# solenoid-shield.net
KiCad netlist of a schematic drawn in EAGLE
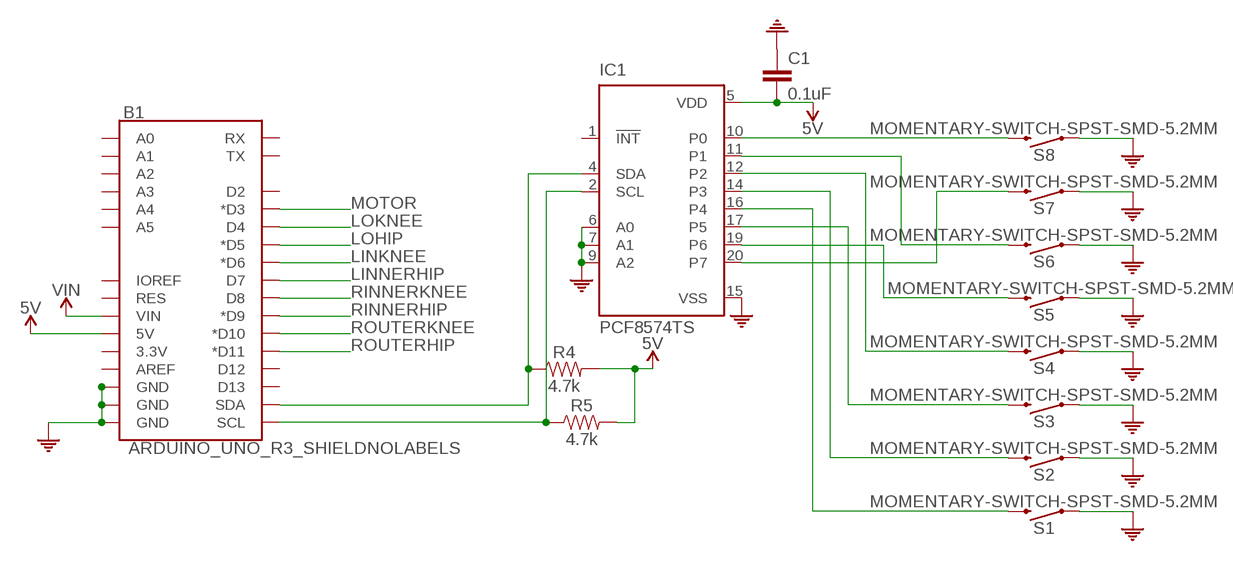
[diagram p0: schematic, sheet 1]
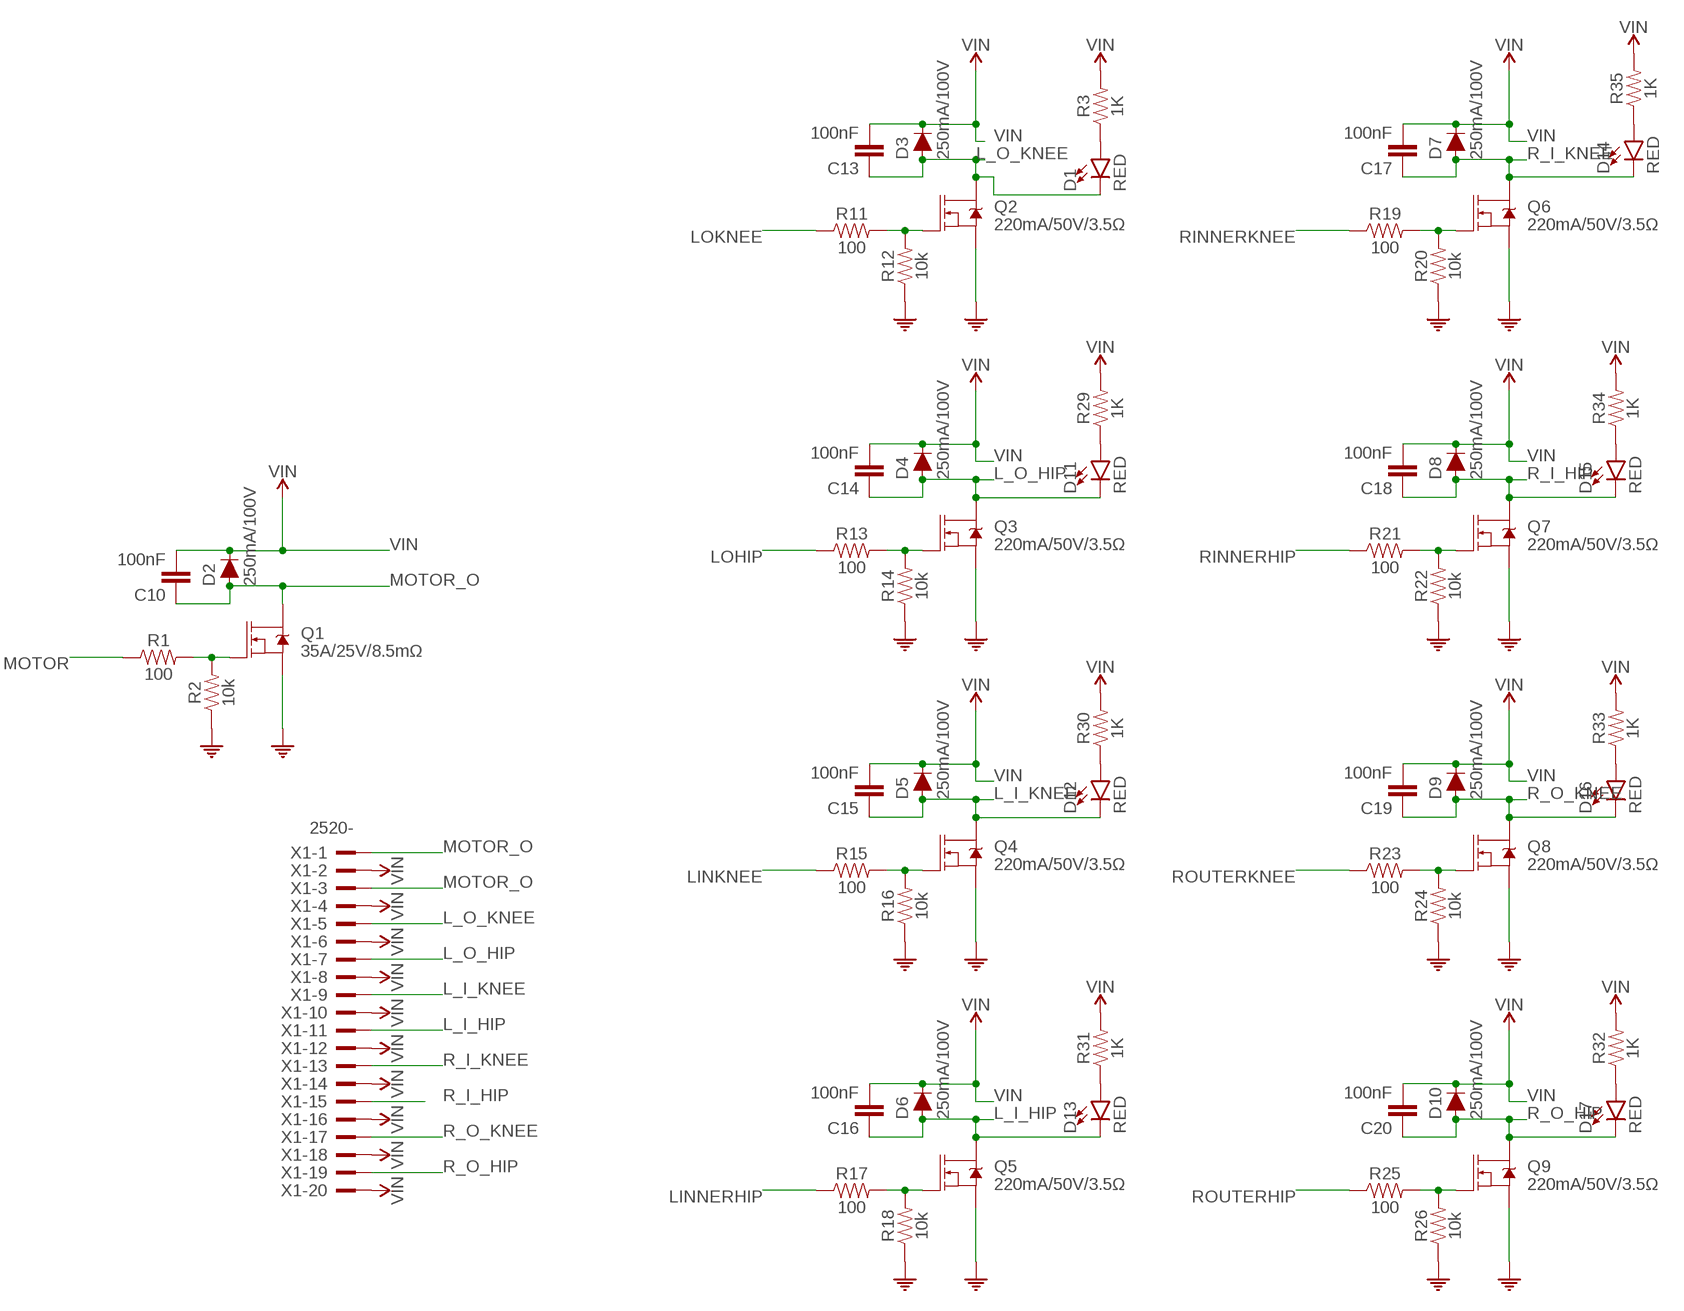
[diagram p1: schematic, sheet 2]

(export (version "E")
  (design (tool "Eeschema 10.0.6"))
  (components
    (comp (ref "B1")
      (value "ARDUINO_UNO_R3_SHIELDNOLABELS")
      (footprint "eagle-import:UNO_R3_SHIELD_NOLABELS")
      (libsource (lib "eagle-import") (part "ARDUINO_UNO_R3_SHIELDNOLABELS"))
    )
    (comp (ref "C1")
      (value "0.1uF")
      (footprint "eagle-import:0603")
      (libsource (lib "eagle-import") (part "0.1UF-0603-25V-5%"))
    )
    (comp (ref "IC1")
      (value "PCF8574TS")
      (footprint "eagle-import:SSOP20")
      (fields (field (name "MPN") "PCF8574TS/3,118"))
      (libsource (lib "eagle-import") (part "PCF8574TS"))
    )
    (comp (ref "R4")
      (value "4.7k")
      (footprint "eagle-import:0603")
      (libsource (lib "eagle-import") (part "4.7KOHM-0603-1/10W-1%"))
    )
    (comp (ref "R5")
      (value "4.7k")
      (footprint "eagle-import:0603")
      (libsource (lib "eagle-import") (part "4.7KOHM-0603-1/10W-1%"))
    )
    (comp (ref "S1")
      (value "MOMENTARY-SWITCH-SPST-SMD-5.2MM")
      (footprint "eagle-import:TACTILE_SWITCH_SMD_5.2MM")
      (libsource (lib "eagle-import") (part "MOMENTARY-SWITCH-SPST-SMD-5.2MM"))
    )
    (comp (ref "S2")
      (value "MOMENTARY-SWITCH-SPST-SMD-5.2MM")
      (footprint "eagle-import:TACTILE_SWITCH_SMD_5.2MM")
      (libsource (lib "eagle-import") (part "MOMENTARY-SWITCH-SPST-SMD-5.2MM"))
    )
    (comp (ref "S3")
      (value "MOMENTARY-SWITCH-SPST-SMD-5.2MM")
      (footprint "eagle-import:TACTILE_SWITCH_SMD_5.2MM")
      (libsource (lib "eagle-import") (part "MOMENTARY-SWITCH-SPST-SMD-5.2MM"))
    )
    (comp (ref "S4")
      (value "MOMENTARY-SWITCH-SPST-SMD-5.2MM")
      (footprint "eagle-import:TACTILE_SWITCH_SMD_5.2MM")
      (libsource (lib "eagle-import") (part "MOMENTARY-SWITCH-SPST-SMD-5.2MM"))
    )
    (comp (ref "S5")
      (value "MOMENTARY-SWITCH-SPST-SMD-5.2MM")
      (footprint "eagle-import:TACTILE_SWITCH_SMD_5.2MM")
      (libsource (lib "eagle-import") (part "MOMENTARY-SWITCH-SPST-SMD-5.2MM"))
    )
    (comp (ref "S6")
      (value "MOMENTARY-SWITCH-SPST-SMD-5.2MM")
      (footprint "eagle-import:TACTILE_SWITCH_SMD_5.2MM")
      (libsource (lib "eagle-import") (part "MOMENTARY-SWITCH-SPST-SMD-5.2MM"))
    )
    (comp (ref "S7")
      (value "MOMENTARY-SWITCH-SPST-SMD-5.2MM")
      (footprint "eagle-import:TACTILE_SWITCH_SMD_5.2MM")
      (libsource (lib "eagle-import") (part "MOMENTARY-SWITCH-SPST-SMD-5.2MM"))
    )
    (comp (ref "S8")
      (value "MOMENTARY-SWITCH-SPST-SMD-5.2MM")
      (footprint "eagle-import:TACTILE_SWITCH_SMD_5.2MM")
      (libsource (lib "eagle-import") (part "MOMENTARY-SWITCH-SPST-SMD-5.2MM"))
    )
    (comp (ref "C10")
      (value "100nF")
      (footprint "eagle-import:C0603-ROUND")
      (fields (field (name "PART_NUMBER") "cl10b104kbnc"))
      (libsource (lib "eagle-import") (part "0015_100NF_0603"))
    )
    (comp (ref "C13")
      (value "100nF")
      (footprint "eagle-import:C0603-ROUND")
      (fields (field (name "PART_NUMBER") "cl10b104kbnc"))
      (libsource (lib "eagle-import") (part "0015_100NF_0603"))
    )
    (comp (ref "C14")
      (value "100nF")
      (footprint "eagle-import:C0603-ROUND")
      (fields (field (name "PART_NUMBER") "cl10b104kbnc"))
      (libsource (lib "eagle-import") (part "0015_100NF_0603"))
    )
    (comp (ref "C15")
      (value "100nF")
      (footprint "eagle-import:C0603-ROUND")
      (fields (field (name "PART_NUMBER") "cl10b104kbnc"))
      (libsource (lib "eagle-import") (part "0015_100NF_0603"))
    )
    (comp (ref "C16")
      (value "100nF")
      (footprint "eagle-import:C0603-ROUND")
      (fields (field (name "PART_NUMBER") "cl10b104kbnc"))
      (libsource (lib "eagle-import") (part "0015_100NF_0603"))
    )
    (comp (ref "C17")
      (value "100nF")
      (footprint "eagle-import:C0603-ROUND")
      (fields (field (name "PART_NUMBER") "cl10b104kbnc"))
      (libsource (lib "eagle-import") (part "0015_100NF_0603"))
    )
    (comp (ref "C18")
      (value "100nF")
      (footprint "eagle-import:C0603-ROUND")
      (fields (field (name "PART_NUMBER") "cl10b104kbnc"))
      (libsource (lib "eagle-import") (part "0015_100NF_0603"))
    )
    (comp (ref "C19")
      (value "100nF")
      (footprint "eagle-import:C0603-ROUND")
      (fields (field (name "PART_NUMBER") "cl10b104kbnc"))
      (libsource (lib "eagle-import") (part "0015_100NF_0603"))
    )
    (comp (ref "C20")
      (value "100nF")
      (footprint "eagle-import:C0603-ROUND")
      (fields (field (name "PART_NUMBER") "cl10b104kbnc"))
      (libsource (lib "eagle-import") (part "0015_100NF_0603"))
    )
    (comp (ref "D1")
      (value "RED")
      (footprint "eagle-import:LED-0603")
      (libsource (lib "eagle-import") (part "LED-RED0603"))
    )
    (comp (ref "D2")
      (value "250mA/100V")
      (footprint "eagle-import:SOD-323")
      (libsource (lib "eagle-import") (part "DIODE-BAS16J"))
    )
    (comp (ref "D3")
      (value "250mA/100V")
      (footprint "eagle-import:SOD-323")
      (libsource (lib "eagle-import") (part "DIODE-BAS16J"))
    )
    (comp (ref "D4")
      (value "250mA/100V")
      (footprint "eagle-import:SOD-323")
      (libsource (lib "eagle-import") (part "DIODE-BAS16J"))
    )
    (comp (ref "D5")
      (value "250mA/100V")
      (footprint "eagle-import:SOD-323")
      (libsource (lib "eagle-import") (part "DIODE-BAS16J"))
    )
    (comp (ref "D6")
      (value "250mA/100V")
      (footprint "eagle-import:SOD-323")
      (libsource (lib "eagle-import") (part "DIODE-BAS16J"))
    )
    (comp (ref "D7")
      (value "250mA/100V")
      (footprint "eagle-import:SOD-323")
      (libsource (lib "eagle-import") (part "DIODE-BAS16J"))
    )
    (comp (ref "D8")
      (value "250mA/100V")
      (footprint "eagle-import:SOD-323")
      (libsource (lib "eagle-import") (part "DIODE-BAS16J"))
    )
    (comp (ref "D9")
      (value "250mA/100V")
      (footprint "eagle-import:SOD-323")
      (libsource (lib "eagle-import") (part "DIODE-BAS16J"))
    )
    (comp (ref "D10")
      (value "250mA/100V")
      (footprint "eagle-import:SOD-323")
      (libsource (lib "eagle-import") (part "DIODE-BAS16J"))
    )
    (comp (ref "D11")
      (value "RED")
      (footprint "eagle-import:LED-0603")
      (libsource (lib "eagle-import") (part "LED-RED0603"))
    )
    (comp (ref "D12")
      (value "RED")
      (footprint "eagle-import:LED-0603")
      (libsource (lib "eagle-import") (part "LED-RED0603"))
    )
    (comp (ref "D13")
      (value "RED")
      (footprint "eagle-import:LED-0603")
      (libsource (lib "eagle-import") (part "LED-RED0603"))
    )
    (comp (ref "D14")
      (value "RED")
      (footprint "eagle-import:LED-0603")
      (libsource (lib "eagle-import") (part "LED-RED0603"))
    )
    (comp (ref "D15")
      (value "RED")
      (footprint "eagle-import:LED-0603")
      (libsource (lib "eagle-import") (part "LED-RED0603"))
    )
    (comp (ref "D16")
      (value "RED")
      (footprint "eagle-import:LED-0603")
      (libsource (lib "eagle-import") (part "LED-RED0603"))
    )
    (comp (ref "D17")
      (value "RED")
      (footprint "eagle-import:LED-0603")
      (libsource (lib "eagle-import") (part "LED-RED0603"))
    )
    (comp (ref "Q1")
      (value "35A/25V/8.5mΩ")
      (footprint "eagle-import:DPAK")
      (libsource (lib "eagle-import") (part "MOSFET-NCH-FDD8780"))
    )
    (comp (ref "Q2")
      (value "220mA/50V/3.5Ω")
      (footprint "eagle-import:SOT23-3")
      (libsource (lib "eagle-import") (part "MOSFET-NCH-BSS138"))
    )
    (comp (ref "Q3")
      (value "220mA/50V/3.5Ω")
      (footprint "eagle-import:SOT23-3")
      (libsource (lib "eagle-import") (part "MOSFET-NCH-BSS138"))
    )
    (comp (ref "Q4")
      (value "220mA/50V/3.5Ω")
      (footprint "eagle-import:SOT23-3")
      (libsource (lib "eagle-import") (part "MOSFET-NCH-BSS138"))
    )
    (comp (ref "Q5")
      (value "220mA/50V/3.5Ω")
      (footprint "eagle-import:SOT23-3")
      (libsource (lib "eagle-import") (part "MOSFET-NCH-BSS138"))
    )
    (comp (ref "Q6")
      (value "220mA/50V/3.5Ω")
      (footprint "eagle-import:SOT23-3")
      (libsource (lib "eagle-import") (part "MOSFET-NCH-BSS138"))
    )
    (comp (ref "Q7")
      (value "220mA/50V/3.5Ω")
      (footprint "eagle-import:SOT23-3")
      (libsource (lib "eagle-import") (part "MOSFET-NCH-BSS138"))
    )
    (comp (ref "Q8")
      (value "220mA/50V/3.5Ω")
      (footprint "eagle-import:SOT23-3")
      (libsource (lib "eagle-import") (part "MOSFET-NCH-BSS138"))
    )
    (comp (ref "Q9")
      (value "220mA/50V/3.5Ω")
      (footprint "eagle-import:SOT23-3")
      (libsource (lib "eagle-import") (part "MOSFET-NCH-BSS138"))
    )
    (comp (ref "R1")
      (value "100")
      (footprint "eagle-import:0603")
      (libsource (lib "eagle-import") (part "100OHM-0603-1/10W-1%"))
    )
    (comp (ref "R2")
      (value "10k")
      (footprint "eagle-import:0603")
      (libsource (lib "eagle-import") (part "10KOHM-0603-1/10W-1%"))
    )
    (comp (ref "R3")
      (value "1K")
      (footprint "eagle-import:0603")
      (libsource (lib "eagle-import") (part "10KOHM-0603-1/10W-1%"))
    )
    (comp (ref "R11")
      (value "100")
      (footprint "eagle-import:0603")
      (libsource (lib "eagle-import") (part "100OHM-0603-1/10W-1%"))
    )
    (comp (ref "R12")
      (value "10k")
      (footprint "eagle-import:0603")
      (libsource (lib "eagle-import") (part "10KOHM-0603-1/10W-1%"))
    )
    (comp (ref "R13")
      (value "100")
      (footprint "eagle-import:0603")
      (libsource (lib "eagle-import") (part "100OHM-0603-1/10W-1%"))
    )
    (comp (ref "R14")
      (value "10k")
      (footprint "eagle-import:0603")
      (libsource (lib "eagle-import") (part "10KOHM-0603-1/10W-1%"))
    )
    (comp (ref "R15")
      (value "100")
      (footprint "eagle-import:0603")
      (libsource (lib "eagle-import") (part "100OHM-0603-1/10W-1%"))
    )
    (comp (ref "R16")
      (value "10k")
      (footprint "eagle-import:0603")
      (libsource (lib "eagle-import") (part "10KOHM-0603-1/10W-1%"))
    )
    (comp (ref "R17")
      (value "100")
      (footprint "eagle-import:0603")
      (libsource (lib "eagle-import") (part "100OHM-0603-1/10W-1%"))
    )
    (comp (ref "R18")
      (value "10k")
      (footprint "eagle-import:0603")
      (libsource (lib "eagle-import") (part "10KOHM-0603-1/10W-1%"))
    )
    (comp (ref "R19")
      (value "100")
      (footprint "eagle-import:0603")
      (libsource (lib "eagle-import") (part "100OHM-0603-1/10W-1%"))
    )
    (comp (ref "R20")
      (value "10k")
      (footprint "eagle-import:0603")
      (libsource (lib "eagle-import") (part "10KOHM-0603-1/10W-1%"))
    )
    (comp (ref "R21")
      (value "100")
      (footprint "eagle-import:0603")
      (libsource (lib "eagle-import") (part "100OHM-0603-1/10W-1%"))
    )
    (comp (ref "R22")
      (value "10k")
      (footprint "eagle-import:0603")
      (libsource (lib "eagle-import") (part "10KOHM-0603-1/10W-1%"))
    )
    (comp (ref "R23")
      (value "100")
      (footprint "eagle-import:0603")
      (libsource (lib "eagle-import") (part "100OHM-0603-1/10W-1%"))
    )
    (comp (ref "R24")
      (value "10k")
      (footprint "eagle-import:0603")
      (libsource (lib "eagle-import") (part "10KOHM-0603-1/10W-1%"))
    )
    (comp (ref "R25")
      (value "100")
      (footprint "eagle-import:0603")
      (libsource (lib "eagle-import") (part "100OHM-0603-1/10W-1%"))
    )
    (comp (ref "R26")
      (value "10k")
      (footprint "eagle-import:0603")
      (libsource (lib "eagle-import") (part "10KOHM-0603-1/10W-1%"))
    )
    (comp (ref "R29")
      (value "1K")
      (footprint "eagle-import:0603")
      (libsource (lib "eagle-import") (part "10KOHM-0603-1/10W-1%"))
    )
    (comp (ref "R30")
      (value "1K")
      (footprint "eagle-import:0603")
      (libsource (lib "eagle-import") (part "10KOHM-0603-1/10W-1%"))
    )
    (comp (ref "R31")
      (value "1K")
      (footprint "eagle-import:0603")
      (libsource (lib "eagle-import") (part "10KOHM-0603-1/10W-1%"))
    )
    (comp (ref "R32")
      (value "1K")
      (footprint "eagle-import:0603")
      (libsource (lib "eagle-import") (part "10KOHM-0603-1/10W-1%"))
    )
    (comp (ref "R33")
      (value "1K")
      (footprint "eagle-import:0603")
      (libsource (lib "eagle-import") (part "10KOHM-0603-1/10W-1%"))
    )
    (comp (ref "R34")
      (value "1K")
      (footprint "eagle-import:0603")
      (libsource (lib "eagle-import") (part "10KOHM-0603-1/10W-1%"))
    )
    (comp (ref "R35")
      (value "1K")
      (footprint "eagle-import:0603")
      (libsource (lib "eagle-import") (part "10KOHM-0603-1/10W-1%"))
    )
    (comp (ref "X1")
      (value "2520-")
      (footprint "eagle-import:PAK100_2500-20")
      (libsource (lib "eagle-import") (part "2520-"))
    )
  )
  (nets
    (net (code "1") (name "5V") (class "Default")
      (node (ref "B1") (pin "5V") (pinfunction "5V_5V") (pintype "bidirectional"))
      (node (ref "C1") (pin "2") (pinfunction "2_2") (pintype "passive"))
      (node (ref "IC1") (pin "5") (pinfunction "VDD_5") (pintype "power_in"))
      (node (ref "R4") (pin "2") (pinfunction "2_2") (pintype "passive"))
      (node (ref "R5") (pin "2") (pinfunction "2_2") (pintype "passive"))
    )
    (net (code "2") (name "COM") (class "Default")
      (node (ref "B1") (pin "GND@0") (pinfunction "GND_GND@0") (pintype "bidirectional"))
      (node (ref "B1") (pin "GND@1") (pinfunction "GND_GND@1") (pintype "bidirectional"))
      (node (ref "B1") (pin "GND@2") (pinfunction "GND_GND@2") (pintype "bidirectional"))
      (node (ref "C1") (pin "1") (pinfunction "1_1") (pintype "passive"))
      (node (ref "IC1") (pin "15") (pinfunction "VSS_15") (pintype "power_in"))
      (node (ref "IC1") (pin "6") (pinfunction "A0_6") (pintype "input"))
      (node (ref "IC1") (pin "7") (pinfunction "A1_7") (pintype "input"))
      (node (ref "IC1") (pin "9") (pinfunction "A2_9") (pintype "input"))
      (node (ref "Q1") (pin "3") (pinfunction "S_3") (pintype "bidirectional"))
      (node (ref "Q2") (pin "2") (pinfunction "S_2") (pintype "bidirectional"))
      (node (ref "Q3") (pin "2") (pinfunction "S_2") (pintype "bidirectional"))
      (node (ref "Q4") (pin "2") (pinfunction "S_2") (pintype "bidirectional"))
      (node (ref "Q5") (pin "2") (pinfunction "S_2") (pintype "bidirectional"))
      (node (ref "Q6") (pin "2") (pinfunction "S_2") (pintype "bidirectional"))
      (node (ref "Q7") (pin "2") (pinfunction "S_2") (pintype "bidirectional"))
      (node (ref "Q8") (pin "2") (pinfunction "S_2") (pintype "bidirectional"))
      (node (ref "Q9") (pin "2") (pinfunction "S_2") (pintype "bidirectional"))
      (node (ref "R12") (pin "1") (pinfunction "1_1") (pintype "passive"))
      (node (ref "R14") (pin "1") (pinfunction "1_1") (pintype "passive"))
      (node (ref "R16") (pin "1") (pinfunction "1_1") (pintype "passive"))
      (node (ref "R18") (pin "1") (pinfunction "1_1") (pintype "passive"))
      (node (ref "R2") (pin "1") (pinfunction "1_1") (pintype "passive"))
      (node (ref "R20") (pin "1") (pinfunction "1_1") (pintype "passive"))
      (node (ref "R22") (pin "1") (pinfunction "1_1") (pintype "passive"))
      (node (ref "R24") (pin "1") (pinfunction "1_1") (pintype "passive"))
      (node (ref "R26") (pin "1") (pinfunction "1_1") (pintype "passive"))
      (node (ref "S1") (pin "1") (pinfunction "1_1") (pintype "passive"))
      (node (ref "S2") (pin "1") (pinfunction "1_1") (pintype "passive"))
      (node (ref "S3") (pin "1") (pinfunction "1_1") (pintype "passive"))
      (node (ref "S4") (pin "1") (pinfunction "1_1") (pintype "passive"))
      (node (ref "S5") (pin "1") (pinfunction "1_1") (pintype "passive"))
      (node (ref "S6") (pin "1") (pinfunction "1_1") (pintype "passive"))
      (node (ref "S7") (pin "1") (pinfunction "1_1") (pintype "passive"))
      (node (ref "S8") (pin "1") (pinfunction "1_1") (pintype "passive"))
    )
    (net (code "3") (name "LINKNEE") (class "Default")
      (node (ref "B1") (pin "D6") (pinfunction "*D6_D6") (pintype "bidirectional"))
      (node (ref "R15") (pin "1") (pinfunction "1_1") (pintype "passive"))
    )
    (net (code "4") (name "LINNERHIP") (class "Default")
      (node (ref "B1") (pin "D7") (pinfunction "D7_D7") (pintype "bidirectional"))
      (node (ref "R17") (pin "1") (pinfunction "1_1") (pintype "passive"))
    )
    (net (code "5") (name "LOHIP") (class "Default")
      (node (ref "B1") (pin "D5") (pinfunction "*D5_D5") (pintype "bidirectional"))
      (node (ref "R13") (pin "1") (pinfunction "1_1") (pintype "passive"))
    )
    (net (code "6") (name "LOKNEE") (class "Default")
      (node (ref "B1") (pin "D4") (pinfunction "D4_D4") (pintype "bidirectional"))
      (node (ref "R11") (pin "1") (pinfunction "1_1") (pintype "passive"))
    )
    (net (code "7") (name "L_I_HIP") (class "Default")
      (node (ref "C16") (pin "1") (pinfunction "1_1") (pintype "passive"))
      (node (ref "D13") (pin "C") (pinfunction "C_C") (pintype "passive"))
      (node (ref "D6") (pin "A") (pinfunction "A_A") (pintype "passive"))
      (node (ref "Q5") (pin "3") (pinfunction "D_3") (pintype "bidirectional"))
      (node (ref "X1") (pin "11") (pinfunction "KL_11") (pintype "passive"))
    )
    (net (code "8") (name "L_I_KNEE") (class "Default")
      (node (ref "C15") (pin "1") (pinfunction "1_1") (pintype "passive"))
      (node (ref "D12") (pin "C") (pinfunction "C_C") (pintype "passive"))
      (node (ref "D5") (pin "A") (pinfunction "A_A") (pintype "passive"))
      (node (ref "Q4") (pin "3") (pinfunction "D_3") (pintype "bidirectional"))
      (node (ref "X1") (pin "9") (pinfunction "KL_9") (pintype "passive"))
    )
    (net (code "9") (name "L_O_HIP") (class "Default")
      (node (ref "C14") (pin "1") (pinfunction "1_1") (pintype "passive"))
      (node (ref "D11") (pin "C") (pinfunction "C_C") (pintype "passive"))
      (node (ref "D4") (pin "A") (pinfunction "A_A") (pintype "passive"))
      (node (ref "Q3") (pin "3") (pinfunction "D_3") (pintype "bidirectional"))
      (node (ref "X1") (pin "7") (pinfunction "KL_7") (pintype "passive"))
    )
    (net (code "10") (name "L_O_KNEE") (class "Default")
      (node (ref "C13") (pin "1") (pinfunction "1_1") (pintype "passive"))
      (node (ref "D1") (pin "C") (pinfunction "C_C") (pintype "passive"))
      (node (ref "D3") (pin "A") (pinfunction "A_A") (pintype "passive"))
      (node (ref "Q2") (pin "3") (pinfunction "D_3") (pintype "bidirectional"))
      (node (ref "X1") (pin "5") (pinfunction "KL_5") (pintype "passive"))
    )
    (net (code "11") (name "MOTOR") (class "Default")
      (node (ref "B1") (pin "D3") (pinfunction "*D3_D3") (pintype "bidirectional"))
      (node (ref "R1") (pin "1") (pinfunction "1_1") (pintype "passive"))
    )
    (net (code "12") (name "MOTOR_O") (class "Default")
      (node (ref "C10") (pin "1") (pinfunction "1_1") (pintype "passive"))
      (node (ref "D2") (pin "A") (pinfunction "A_A") (pintype "passive"))
      (node (ref "Q1") (pin "4") (pinfunction "D_4") (pintype "bidirectional"))
      (node (ref "X1") (pin "1") (pinfunction "KL_1") (pintype "passive"))
      (node (ref "X1") (pin "3") (pinfunction "KL_3") (pintype "passive"))
    )
    (net (code "13") (name "Net-(D1-PadA)") (class "Default")
      (node (ref "D1") (pin "A") (pinfunction "A_A") (pintype "passive"))
      (node (ref "R3") (pin "1") (pinfunction "1_1") (pintype "passive"))
    )
    (net (code "14") (name "Net-(D11-PadA)") (class "Default")
      (node (ref "D11") (pin "A") (pinfunction "A_A") (pintype "passive"))
      (node (ref "R29") (pin "1") (pinfunction "1_1") (pintype "passive"))
    )
    (net (code "15") (name "Net-(D12-PadA)") (class "Default")
      (node (ref "D12") (pin "A") (pinfunction "A_A") (pintype "passive"))
      (node (ref "R30") (pin "1") (pinfunction "1_1") (pintype "passive"))
    )
    (net (code "16") (name "Net-(D13-PadA)") (class "Default")
      (node (ref "D13") (pin "A") (pinfunction "A_A") (pintype "passive"))
      (node (ref "R31") (pin "1") (pinfunction "1_1") (pintype "passive"))
    )
    (net (code "17") (name "Net-(D14-PadA)") (class "Default")
      (node (ref "D14") (pin "A") (pinfunction "A_A") (pintype "passive"))
      (node (ref "R35") (pin "1") (pinfunction "1_1") (pintype "passive"))
    )
    (net (code "18") (name "Net-(D15-PadA)") (class "Default")
      (node (ref "D15") (pin "A") (pinfunction "A_A") (pintype "passive"))
      (node (ref "R34") (pin "1") (pinfunction "1_1") (pintype "passive"))
    )
    (net (code "19") (name "Net-(D16-PadA)") (class "Default")
      (node (ref "D16") (pin "A") (pinfunction "A_A") (pintype "passive"))
      (node (ref "R33") (pin "1") (pinfunction "1_1") (pintype "passive"))
    )
    (net (code "20") (name "Net-(D17-PadA)") (class "Default")
      (node (ref "D17") (pin "A") (pinfunction "A_A") (pintype "passive"))
      (node (ref "R32") (pin "1") (pinfunction "1_1") (pintype "passive"))
    )
    (net (code "21") (name "Net-(IC1-P0)") (class "Default")
      (node (ref "IC1") (pin "10") (pinfunction "P0_10") (pintype "bidirectional"))
      (node (ref "S8") (pin "3") (pinfunction "2_3") (pintype "passive"))
    )
    (net (code "22") (name "Net-(IC1-P1)") (class "Default")
      (node (ref "IC1") (pin "11") (pinfunction "P1_11") (pintype "bidirectional"))
      (node (ref "S6") (pin "3") (pinfunction "2_3") (pintype "passive"))
    )
    (net (code "23") (name "Net-(IC1-P2)") (class "Default")
      (node (ref "IC1") (pin "12") (pinfunction "P2_12") (pintype "bidirectional"))
      (node (ref "S4") (pin "3") (pinfunction "2_3") (pintype "passive"))
    )
    (net (code "24") (name "Net-(IC1-P3)") (class "Default")
      (node (ref "IC1") (pin "14") (pinfunction "P3_14") (pintype "bidirectional"))
      (node (ref "S2") (pin "3") (pinfunction "2_3") (pintype "passive"))
    )
    (net (code "25") (name "Net-(IC1-P4)") (class "Default")
      (node (ref "IC1") (pin "16") (pinfunction "P4_16") (pintype "bidirectional"))
      (node (ref "S1") (pin "3") (pinfunction "2_3") (pintype "passive"))
    )
    (net (code "26") (name "Net-(IC1-P5)") (class "Default")
      (node (ref "IC1") (pin "17") (pinfunction "P5_17") (pintype "bidirectional"))
      (node (ref "S3") (pin "3") (pinfunction "2_3") (pintype "passive"))
    )
    (net (code "27") (name "Net-(IC1-P6)") (class "Default")
      (node (ref "IC1") (pin "19") (pinfunction "P6_19") (pintype "bidirectional"))
      (node (ref "S5") (pin "3") (pinfunction "2_3") (pintype "passive"))
    )
    (net (code "28") (name "Net-(IC1-P7)") (class "Default")
      (node (ref "IC1") (pin "20") (pinfunction "P7_20") (pintype "bidirectional"))
      (node (ref "S7") (pin "3") (pinfunction "2_3") (pintype "passive"))
    )
    (net (code "29") (name "Net-(IC1-SCL)") (class "Default")
      (node (ref "B1") (pin "SCL") (pinfunction "SCL_SCL") (pintype "bidirectional"))
      (node (ref "IC1") (pin "2") (pinfunction "SCL_2") (pintype "input"))
      (node (ref "R5") (pin "1") (pinfunction "1_1") (pintype "passive"))
    )
    (net (code "30") (name "Net-(IC1-SDA)") (class "Default")
      (node (ref "B1") (pin "SDA") (pinfunction "SDA_SDA") (pintype "bidirectional"))
      (node (ref "IC1") (pin "4") (pinfunction "SDA_4") (pintype "bidirectional"))
      (node (ref "R4") (pin "1") (pinfunction "1_1") (pintype "passive"))
    )
    (net (code "31") (name "Net-(Q1-G)") (class "Default")
      (node (ref "Q1") (pin "1") (pinfunction "G_1") (pintype "bidirectional"))
      (node (ref "R1") (pin "2") (pinfunction "2_2") (pintype "passive"))
      (node (ref "R2") (pin "2") (pinfunction "2_2") (pintype "passive"))
    )
    (net (code "32") (name "Net-(Q2-G)") (class "Default")
      (node (ref "Q2") (pin "1") (pinfunction "G_1") (pintype "bidirectional"))
      (node (ref "R11") (pin "2") (pinfunction "2_2") (pintype "passive"))
      (node (ref "R12") (pin "2") (pinfunction "2_2") (pintype "passive"))
    )
    (net (code "33") (name "Net-(Q3-G)") (class "Default")
      (node (ref "Q3") (pin "1") (pinfunction "G_1") (pintype "bidirectional"))
      (node (ref "R13") (pin "2") (pinfunction "2_2") (pintype "passive"))
      (node (ref "R14") (pin "2") (pinfunction "2_2") (pintype "passive"))
    )
    (net (code "34") (name "Net-(Q4-G)") (class "Default")
      (node (ref "Q4") (pin "1") (pinfunction "G_1") (pintype "bidirectional"))
      (node (ref "R15") (pin "2") (pinfunction "2_2") (pintype "passive"))
      (node (ref "R16") (pin "2") (pinfunction "2_2") (pintype "passive"))
    )
    (net (code "35") (name "Net-(Q5-G)") (class "Default")
      (node (ref "Q5") (pin "1") (pinfunction "G_1") (pintype "bidirectional"))
      (node (ref "R17") (pin "2") (pinfunction "2_2") (pintype "passive"))
      (node (ref "R18") (pin "2") (pinfunction "2_2") (pintype "passive"))
    )
    (net (code "36") (name "Net-(Q6-G)") (class "Default")
      (node (ref "Q6") (pin "1") (pinfunction "G_1") (pintype "bidirectional"))
      (node (ref "R19") (pin "2") (pinfunction "2_2") (pintype "passive"))
      (node (ref "R20") (pin "2") (pinfunction "2_2") (pintype "passive"))
    )
    (net (code "37") (name "Net-(Q7-G)") (class "Default")
      (node (ref "Q7") (pin "1") (pinfunction "G_1") (pintype "bidirectional"))
      (node (ref "R21") (pin "2") (pinfunction "2_2") (pintype "passive"))
      (node (ref "R22") (pin "2") (pinfunction "2_2") (pintype "passive"))
    )
    (net (code "38") (name "Net-(Q8-G)") (class "Default")
      (node (ref "Q8") (pin "1") (pinfunction "G_1") (pintype "bidirectional"))
      (node (ref "R23") (pin "2") (pinfunction "2_2") (pintype "passive"))
      (node (ref "R24") (pin "2") (pinfunction "2_2") (pintype "passive"))
    )
    (net (code "39") (name "Net-(Q9-G)") (class "Default")
      (node (ref "Q9") (pin "1") (pinfunction "G_1") (pintype "bidirectional"))
      (node (ref "R25") (pin "2") (pinfunction "2_2") (pintype "passive"))
      (node (ref "R26") (pin "2") (pinfunction "2_2") (pintype "passive"))
    )
    (net (code "40") (name "RINNERHIP") (class "Default")
      (node (ref "B1") (pin "D9") (pinfunction "*D9_D9") (pintype "bidirectional"))
      (node (ref "R21") (pin "1") (pinfunction "1_1") (pintype "passive"))
    )
    (net (code "41") (name "RINNERKNEE") (class "Default")
      (node (ref "B1") (pin "D8") (pinfunction "D8_D8") (pintype "bidirectional"))
      (node (ref "R19") (pin "1") (pinfunction "1_1") (pintype "passive"))
    )
    (net (code "42") (name "ROUTERHIP") (class "Default")
      (node (ref "B1") (pin "D11") (pinfunction "*D11_D11") (pintype "bidirectional"))
      (node (ref "R25") (pin "1") (pinfunction "1_1") (pintype "passive"))
    )
    (net (code "43") (name "ROUTERKNEE") (class "Default")
      (node (ref "B1") (pin "D10") (pinfunction "*D10_D10") (pintype "bidirectional"))
      (node (ref "R23") (pin "1") (pinfunction "1_1") (pintype "passive"))
    )
    (net (code "44") (name "R_I_HIP") (class "Default")
      (node (ref "C18") (pin "1") (pinfunction "1_1") (pintype "passive"))
      (node (ref "D15") (pin "C") (pinfunction "C_C") (pintype "passive"))
      (node (ref "D8") (pin "A") (pinfunction "A_A") (pintype "passive"))
      (node (ref "Q7") (pin "3") (pinfunction "D_3") (pintype "bidirectional"))
      (node (ref "X1") (pin "15") (pinfunction "KL_15") (pintype "passive"))
    )
    (net (code "45") (name "R_I_KNEE") (class "Default")
      (node (ref "C17") (pin "1") (pinfunction "1_1") (pintype "passive"))
      (node (ref "D14") (pin "C") (pinfunction "C_C") (pintype "passive"))
      (node (ref "D7") (pin "A") (pinfunction "A_A") (pintype "passive"))
      (node (ref "Q6") (pin "3") (pinfunction "D_3") (pintype "bidirectional"))
      (node (ref "X1") (pin "13") (pinfunction "KL_13") (pintype "passive"))
    )
    (net (code "46") (name "R_O_HIP") (class "Default")
      (node (ref "C20") (pin "1") (pinfunction "1_1") (pintype "passive"))
      (node (ref "D10") (pin "A") (pinfunction "A_A") (pintype "passive"))
      (node (ref "D17") (pin "C") (pinfunction "C_C") (pintype "passive"))
      (node (ref "Q9") (pin "3") (pinfunction "D_3") (pintype "bidirectional"))
      (node (ref "X1") (pin "19") (pinfunction "KL_19") (pintype "passive"))
    )
    (net (code "47") (name "R_O_KNEE") (class "Default")
      (node (ref "C19") (pin "1") (pinfunction "1_1") (pintype "passive"))
      (node (ref "D16") (pin "C") (pinfunction "C_C") (pintype "passive"))
      (node (ref "D9") (pin "A") (pinfunction "A_A") (pintype "passive"))
      (node (ref "Q8") (pin "3") (pinfunction "D_3") (pintype "bidirectional"))
      (node (ref "X1") (pin "17") (pinfunction "KL_17") (pintype "passive"))
    )
    (net (code "48") (name "VIN") (class "Default")
      (node (ref "B1") (pin "VIN") (pinfunction "VIN_VIN") (pintype "bidirectional"))
      (node (ref "C10") (pin "2") (pinfunction "2_2") (pintype "passive"))
      (node (ref "C13") (pin "2") (pinfunction "2_2") (pintype "passive"))
      (node (ref "C14") (pin "2") (pinfunction "2_2") (pintype "passive"))
      (node (ref "C15") (pin "2") (pinfunction "2_2") (pintype "passive"))
      (node (ref "C16") (pin "2") (pinfunction "2_2") (pintype "passive"))
      (node (ref "C17") (pin "2") (pinfunction "2_2") (pintype "passive"))
      (node (ref "C18") (pin "2") (pinfunction "2_2") (pintype "passive"))
      (node (ref "C19") (pin "2") (pinfunction "2_2") (pintype "passive"))
      (node (ref "C20") (pin "2") (pinfunction "2_2") (pintype "passive"))
      (node (ref "D10") (pin "C") (pinfunction "C_C") (pintype "passive"))
      (node (ref "D2") (pin "C") (pinfunction "C_C") (pintype "passive"))
      (node (ref "D3") (pin "C") (pinfunction "C_C") (pintype "passive"))
      (node (ref "D4") (pin "C") (pinfunction "C_C") (pintype "passive"))
      (node (ref "D5") (pin "C") (pinfunction "C_C") (pintype "passive"))
      (node (ref "D6") (pin "C") (pinfunction "C_C") (pintype "passive"))
      (node (ref "D7") (pin "C") (pinfunction "C_C") (pintype "passive"))
      (node (ref "D8") (pin "C") (pinfunction "C_C") (pintype "passive"))
      (node (ref "D9") (pin "C") (pinfunction "C_C") (pintype "passive"))
      (node (ref "R29") (pin "2") (pinfunction "2_2") (pintype "passive"))
      (node (ref "R3") (pin "2") (pinfunction "2_2") (pintype "passive"))
      (node (ref "R30") (pin "2") (pinfunction "2_2") (pintype "passive"))
      (node (ref "R31") (pin "2") (pinfunction "2_2") (pintype "passive"))
      (node (ref "R32") (pin "2") (pinfunction "2_2") (pintype "passive"))
      (node (ref "R33") (pin "2") (pinfunction "2_2") (pintype "passive"))
      (node (ref "R34") (pin "2") (pinfunction "2_2") (pintype "passive"))
      (node (ref "R35") (pin "2") (pinfunction "2_2") (pintype "passive"))
      (node (ref "X1") (pin "10") (pinfunction "KL_10") (pintype "passive"))
      (node (ref "X1") (pin "12") (pinfunction "KL_12") (pintype "passive"))
      (node (ref "X1") (pin "14") (pinfunction "KL_14") (pintype "passive"))
      (node (ref "X1") (pin "16") (pinfunction "KL_16") (pintype "passive"))
      (node (ref "X1") (pin "18") (pinfunction "KL_18") (pintype "passive"))
      (node (ref "X1") (pin "2") (pinfunction "KL_2") (pintype "passive"))
      (node (ref "X1") (pin "20") (pinfunction "KL_20") (pintype "passive"))
      (node (ref "X1") (pin "4") (pinfunction "KL_4") (pintype "passive"))
      (node (ref "X1") (pin "6") (pinfunction "KL_6") (pintype "passive"))
      (node (ref "X1") (pin "8") (pinfunction "KL_8") (pintype "passive"))
    )
    (net (code "49") (name "unconnected-(B1-Pad3.3V)") (class "Default")
      (node (ref "B1") (pin "3.3V") (pinfunction "3.3V_3.3V") (pintype "bidirectional"))
    )
    (net (code "50") (name "unconnected-(B1-PadA0)") (class "Default")
      (node (ref "B1") (pin "A0") (pinfunction "A0_A0") (pintype "bidirectional"))
    )
    (net (code "51") (name "unconnected-(B1-PadA1)") (class "Default")
      (node (ref "B1") (pin "A1") (pinfunction "A1_A1") (pintype "bidirectional"))
    )
    (net (code "52") (name "unconnected-(B1-PadA2)") (class "Default")
      (node (ref "B1") (pin "A2") (pinfunction "A2_A2") (pintype "bidirectional"))
    )
    (net (code "53") (name "unconnected-(B1-PadA3)") (class "Default")
      (node (ref "B1") (pin "A3") (pinfunction "A3_A3") (pintype "bidirectional"))
    )
    (net (code "54") (name "unconnected-(B1-PadA4)") (class "Default")
      (node (ref "B1") (pin "A4") (pinfunction "A4_A4") (pintype "bidirectional"))
    )
    (net (code "55") (name "unconnected-(B1-PadA5)") (class "Default")
      (node (ref "B1") (pin "A5") (pinfunction "A5_A5") (pintype "bidirectional"))
    )
    (net (code "56") (name "unconnected-(B1-PadAREF)") (class "Default")
      (node (ref "B1") (pin "AREF") (pinfunction "AREF_AREF") (pintype "bidirectional"))
    )
    (net (code "57") (name "unconnected-(B1-PadD2)") (class "Default")
      (node (ref "B1") (pin "D2") (pinfunction "D2_D2") (pintype "bidirectional"))
    )
    (net (code "58") (name "unconnected-(B1-PadD12)") (class "Default")
      (node (ref "B1") (pin "D12") (pinfunction "D12_D12") (pintype "bidirectional"))
    )
    (net (code "59") (name "unconnected-(B1-PadD13)") (class "Default")
      (node (ref "B1") (pin "D13") (pinfunction "D13_D13") (pintype "bidirectional"))
    )
    (net (code "60") (name "unconnected-(B1-PadIOREF)") (class "Default")
      (node (ref "B1") (pin "IOREF") (pinfunction "IOREF_IOREF") (pintype "bidirectional"))
    )
    (net (code "61") (name "unconnected-(B1-PadRES)") (class "Default")
      (node (ref "B1") (pin "RES") (pinfunction "RES_RES") (pintype "bidirectional"))
    )
    (net (code "62") (name "unconnected-(B1-PadRX)") (class "Default")
      (node (ref "B1") (pin "RX") (pinfunction "RX_RX") (pintype "bidirectional"))
    )
    (net (code "63") (name "unconnected-(B1-PadTX)") (class "Default")
      (node (ref "B1") (pin "TX") (pinfunction "TX_TX") (pintype "bidirectional"))
    )
    (net (code "64") (name "unconnected-(IC1-~{INT}-Pad1)") (class "Default")
      (node (ref "IC1") (pin "1") (pinfunction "~{INT}_1") (pintype "output"))
    )
  )
)
